# FLEX_CONN.net
KiCad netlist of a schematic drawn in EAGLE
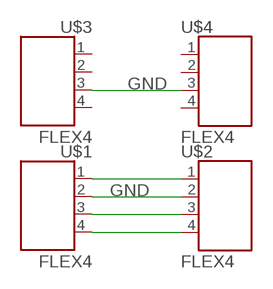
[diagram p0: schematic, sheet 1]

(export (version "E")
  (design (tool "Eeschema 10.0.6"))
  (components
    (comp (ref "U$1")
      (value "FLEX4")
      (footprint "eagle-import:FLEX4")
      (libsource (lib "eagle-import") (part "FLEX4"))
    )
    (comp (ref "U$2")
      (value "FLEX4")
      (footprint "eagle-import:FLEX4")
      (libsource (lib "eagle-import") (part "FLEX4"))
    )
    (comp (ref "U$3")
      (value "FLEX4")
      (footprint "eagle-import:FLEX4")
      (libsource (lib "eagle-import") (part "FLEX4"))
    )
    (comp (ref "U$4")
      (value "FLEX4")
      (footprint "eagle-import:FLEX4")
      (libsource (lib "eagle-import") (part "FLEX4"))
    )
  )
  (nets
    (net (code "1") (name "/GND") (class "Default")
      (node (ref "U$1") (pin "2") (pinfunction "2_2") (pintype "passive"))
      (node (ref "U$2") (pin "2") (pinfunction "2_2") (pintype "passive"))
      (node (ref "U$3") (pin "3") (pinfunction "3_3") (pintype "passive"))
      (node (ref "U$4") (pin "3") (pinfunction "3_3") (pintype "passive"))
    )
    (net (code "2") (name "Net-(U$1-Pad1)") (class "Default")
      (node (ref "U$1") (pin "1") (pinfunction "1_1") (pintype "passive"))
      (node (ref "U$2") (pin "1") (pinfunction "1_1") (pintype "passive"))
    )
    (net (code "3") (name "Net-(U$1-Pad3)") (class "Default")
      (node (ref "U$1") (pin "3") (pinfunction "3_3") (pintype "passive"))
      (node (ref "U$2") (pin "3") (pinfunction "3_3") (pintype "passive"))
    )
    (net (code "4") (name "Net-(U$1-Pad4)") (class "Default")
      (node (ref "U$1") (pin "4") (pinfunction "4_4") (pintype "passive"))
      (node (ref "U$2") (pin "4") (pinfunction "4_4") (pintype "passive"))
    )
    (net (code "5") (name "unconnected-(U$3-Pad1)") (class "Default")
      (node (ref "U$3") (pin "1") (pinfunction "1_1") (pintype "passive"))
    )
    (net (code "6") (name "unconnected-(U$3-Pad2)") (class "Default")
      (node (ref "U$3") (pin "2") (pinfunction "2_2") (pintype "passive"))
    )
    (net (code "7") (name "unconnected-(U$3-Pad4)") (class "Default")
      (node (ref "U$3") (pin "4") (pinfunction "4_4") (pintype "passive"))
    )
    (net (code "8") (name "unconnected-(U$4-Pad1)") (class "Default")
      (node (ref "U$4") (pin "1") (pinfunction "1_1") (pintype "passive"))
    )
    (net (code "9") (name "unconnected-(U$4-Pad2)") (class "Default")
      (node (ref "U$4") (pin "2") (pinfunction "2_2") (pintype "passive"))
    )
    (net (code "10") (name "unconnected-(U$4-Pad4)") (class "Default")
      (node (ref "U$4") (pin "4") (pinfunction "4_4") (pintype "passive"))
    )
  )
)
